# Opioid_-_Power_-_rev_A0.net
KiCad netlist of a schematic drawn in Altium Designer
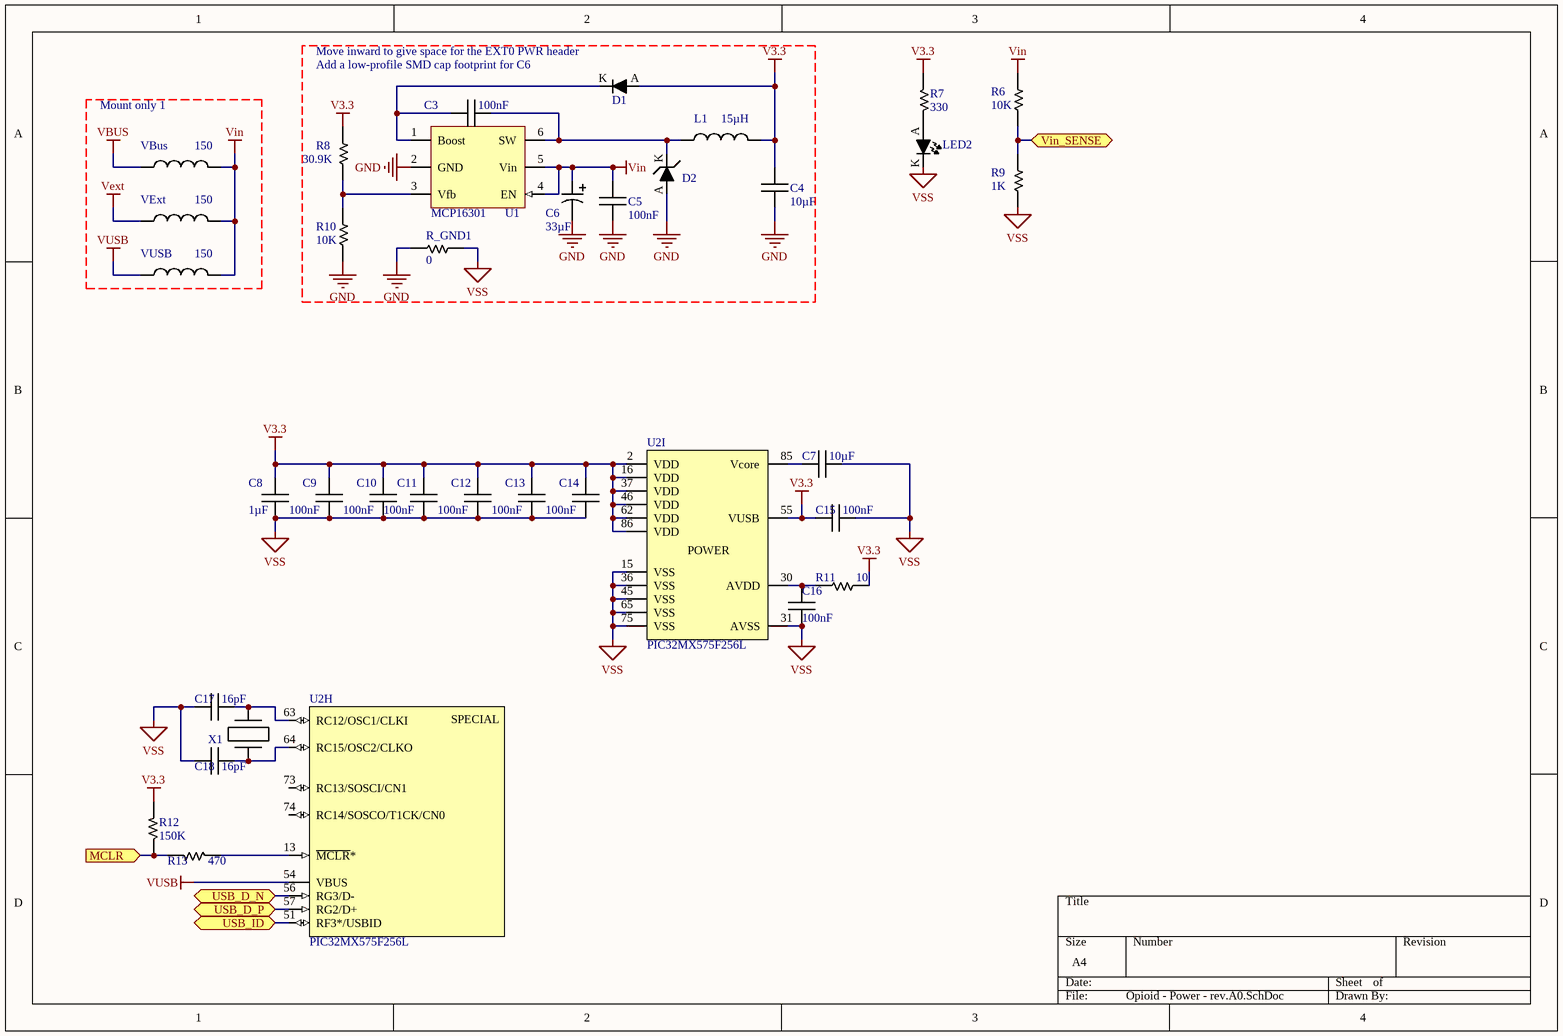
[diagram p0: Opioid - Power - rev.A0.SchDoc]

(export (version "E")
  (design (tool "Eeschema 10.0.6"))
  (components
    (comp (ref "C3") (value "100nF") (footprint "CAPC1608N") (libsource (lib "Megaxone") (part "Capacitor")))
    (comp (ref "C4") (value "10µF") (footprint "CAPC2012N") (libsource (lib "Megaxone") (part "Capacitor")))
    (comp (ref "C5") (value "100nF") (footprint "CAPC1608N") (libsource (lib "Megaxone") (part "Capacitor")))
    (comp (ref "C6")
      (value "33µF")
      (footprint "CAPPR2-5x11")
      (libsource (lib "Megaxone") (part "Capacitor Polarised"))
    )
    (comp (ref "C7") (value "10µF") (footprint "CAPC2012N") (libsource (lib "Megaxone") (part "Capacitor")))
    (comp (ref "C8") (value "1µF") (footprint "CAPC1608N") (libsource (lib "Megaxone") (part "Capacitor")))
    (comp (ref "C9") (value "100nF") (footprint "CAPC1608N") (libsource (lib "Megaxone") (part "Capacitor")))
    (comp (ref "C10") (value "100nF") (footprint "CAPC1608N") (libsource (lib "Megaxone") (part "Capacitor")))
    (comp (ref "C11") (value "100nF") (footprint "CAPC1608N") (libsource (lib "Megaxone") (part "Capacitor")))
    (comp (ref "C12") (value "100nF") (footprint "CAPC1608N") (libsource (lib "Megaxone") (part "Capacitor")))
    (comp (ref "C13") (value "100nF") (footprint "CAPC1608N") (libsource (lib "Megaxone") (part "Capacitor")))
    (comp (ref "C14") (value "100nF") (footprint "CAPC1608N") (libsource (lib "Megaxone") (part "Capacitor")))
    (comp (ref "C15") (value "100nF") (footprint "CAPC1608N") (libsource (lib "Megaxone") (part "Capacitor")))
    (comp (ref "C16") (value "100nF") (footprint "CAPC1608N") (libsource (lib "Megaxone") (part "Capacitor")))
    (comp (ref "C17") (value "16pF") (footprint "CAPC2012N") (libsource (lib "Megaxone") (part "Capacitor")))
    (comp (ref "C18") (value "16pF") (footprint "CAPC2012N") (libsource (lib "Megaxone") (part "Capacitor")))
    (comp (ref "D1") (value "Diode") (footprint "SOT323") (libsource (lib "Megaxone") (part "Diode")))
    (comp (ref "D2")
      (value "Schottky Diode")
      (footprint "DO-214AC")
      (libsource (lib "Megaxone") (part "Schottky Diode"))
    )
    (comp (ref "L1")
      (value "15µH")
      (footprint "INDUCTOR 6×6mm Taiyo Yuden")
      (libsource (lib "Megaxone") (part "Inductor"))
    )
    (comp (ref "LED2") (value "~") (footprint "LED 1608m") (libsource (lib "Megaxone") (part "LED")))
    (comp (ref "R6") (value "10K") (footprint "RESC1608N") (libsource (lib "") (part "Resistor_1")))
    (comp (ref "R7") (value "330") (footprint "RESC1608N") (libsource (lib "") (part "Resistor_2")))
    (comp (ref "R8") (value "30.9K") (footprint "RESC1608N") (libsource (lib "") (part "Resistor_1")))
    (comp (ref "R9") (value "1K") (footprint "RESC1608N") (libsource (lib "") (part "Resistor_1")))
    (comp (ref "R10") (value "10K") (footprint "RESC1608N") (libsource (lib "") (part "Resistor_1")))
    (comp (ref "R11") (value "10") (footprint "RESC1608N") (libsource (lib "Megaxone") (part "Resistor")))
    (comp (ref "R12") (value "150K") (footprint "RESC1608N") (libsource (lib "Megaxone") (part "Resistor")))
    (comp (ref "R13") (value "470") (footprint "RESC1608N") (libsource (lib "") (part "Resistor_3")))
    (comp (ref "R_GND1") (value "0") (footprint "RESC1608N") (libsource (lib "Megaxone") (part "Resistor")))
    (comp (ref "U1")
      (value "MCP16301")
      (footprint "SOT23-6_N")
      (libsource (lib "Megaxone") (part "MCP16301"))
    )
    (comp (ref "U2")
      (value "PIC32MX575F256L")
      (footprint "TQFP-PT100_N")
      (libsource (lib "Megaxone") (part "PIC32MX575F256L"))
    )
    (comp (ref "VBus") (value "150") (footprint "INDC1608N") (libsource (lib "Megaxone") (part "Inductor")))
    (comp (ref "VExt") (value "150") (footprint "INDC1608N") (libsource (lib "Megaxone") (part "Inductor")))
    (comp (ref "VUSB") (value "150") (footprint "INDC1608N") (libsource (lib "Megaxone") (part "Inductor")))
    (comp (ref "X1")
      (value "Crystal")
      (footprint "BCY-W2/D3.1")
      (libsource (lib "Megaxone") (part "Crystal"))
    )
  )
  (nets
    (net (code "1") (name "/MCLR") (class "Default")
      (node (ref "R12") (pin "1") (pinfunction "1_1") (pintype "passive"))
      (node (ref "R13") (pin "2") (pinfunction "2_2") (pintype "passive"))
    )
    (net (code "2") (name "/USB_D_N") (class "Default")
      (node (ref "U2") (pin "56") (pinfunction "RG3/D-_56") (pintype "input"))
    )
    (net (code "3") (name "/USB_D_P") (class "Default")
      (node (ref "U2") (pin "57") (pinfunction "RG2/D+_57") (pintype "input"))
    )
    (net (code "4") (name "/USB_ID") (class "Default")
      (node (ref "U2") (pin "51") (pinfunction "RF3*/USBID_51") (pintype "bidirectional"))
    )
    (net (code "5") (name "/Vin_SENSE") (class "Default")
      (node (ref "R6") (pin "1") (pinfunction "1_1") (pintype "passive"))
      (node (ref "R9") (pin "2") (pinfunction "2_2") (pintype "passive"))
    )
    (net (code "6") (name "GND") (class "Default")
      (node (ref "C4") (pin "1") (pinfunction "1_1") (pintype "passive"))
      (node (ref "C5") (pin "2") (pinfunction "2_2") (pintype "passive"))
      (node (ref "C6") (pin "2") (pinfunction "2_2") (pintype "passive"))
      (node (ref "D2") (pin "A") (pinfunction "Anode_A") (pintype "power_in"))
      (node (ref "R10") (pin "1") (pinfunction "1_1") (pintype "passive"))
      (node (ref "R_GND1") (pin "1") (pinfunction "1_1") (pintype "passive"))
      (node (ref "U1") (pin "2") (pinfunction "GND_2") (pintype "power_in"))
    )
    (net (code "7") (name "Net-(D2-Kathode)") (class "Default")
      (node (ref "C3") (pin "1") (pinfunction "1_1") (pintype "passive"))
      (node (ref "D2") (pin "K") (pinfunction "Kathode_K") (pintype "power_in"))
      (node (ref "L1") (pin "1") (pinfunction "1_1") (pintype "passive"))
      (node (ref "U1") (pin "6") (pinfunction "SW_6") (pintype "power_in"))
    )
    (net (code "8") (name "Net-(LED2-PadA)") (class "Default")
      (node (ref "LED2") (pin "A") (pinfunction "A_A") (pintype "passive"))
      (node (ref "R7") (pin "2") (pinfunction "2_2") (pintype "passive"))
    )
    (net (code "9") (name "Net-(U1-Boost)") (class "Default")
      (node (ref "C3") (pin "2") (pinfunction "2_2") (pintype "passive"))
      (node (ref "D1") (pin "K") (pinfunction "K_K") (pintype "power_in"))
      (node (ref "U1") (pin "1") (pinfunction "Boost_1") (pintype "passive"))
    )
    (net (code "10") (name "Net-(U1-Vfb)") (class "Default")
      (node (ref "R10") (pin "2") (pinfunction "2_2") (pintype "passive"))
      (node (ref "R8") (pin "1") (pinfunction "1_1") (pintype "passive"))
      (node (ref "U1") (pin "3") (pinfunction "Vfb_3") (pintype "passive"))
    )
    (net (code "11") (name "Net-(U2H-RC12{slash}OSC1{slash}CLKI)") (class "Default")
      (node (ref "C17") (pin "1") (pinfunction "1_1") (pintype "passive"))
      (node (ref "U2") (pin "63") (pinfunction "RC12/OSC1/CLKI_63") (pintype "bidirectional"))
      (node (ref "X1") (pin "2") (pinfunction "2_2") (pintype "passive"))
    )
    (net (code "12") (name "Net-(U2H-RC15{slash}OSC2{slash}CLKO)") (class "Default")
      (node (ref "C18") (pin "1") (pinfunction "1_1") (pintype "passive"))
      (node (ref "U2") (pin "64") (pinfunction "RC15/OSC2/CLKO_64") (pintype "bidirectional"))
      (node (ref "X1") (pin "1") (pinfunction "1_1") (pintype "passive"))
    )
    (net (code "13") (name "Net-(U2H-~{MCLR}*)") (class "Default")
      (node (ref "R13") (pin "1") (pinfunction "1_1") (pintype "passive"))
      (node (ref "U2") (pin "13") (pinfunction "~{MCLR}*_13") (pintype "input"))
    )
    (net (code "14") (name "Net-(U2I-AVDD)") (class "Default")
      (node (ref "C16") (pin "2") (pinfunction "2_2") (pintype "passive"))
      (node (ref "R11") (pin "1") (pinfunction "1_1") (pintype "passive"))
      (node (ref "U2") (pin "30") (pinfunction "AVDD_30") (pintype "power_in"))
    )
    (net (code "15") (name "Net-(U2I-Vcore)") (class "Default")
      (node (ref "C7") (pin "2") (pinfunction "2_2") (pintype "passive"))
      (node (ref "U2") (pin "85") (pinfunction "Vcore_85") (pintype "power_in"))
    )
    (net (code "16") (name "V3.3") (class "Default")
      (node (ref "C10") (pin "2") (pinfunction "2_2") (pintype "passive"))
      (node (ref "C11") (pin "2") (pinfunction "2_2") (pintype "passive"))
      (node (ref "C12") (pin "2") (pinfunction "2_2") (pintype "passive"))
      (node (ref "C13") (pin "2") (pinfunction "2_2") (pintype "passive"))
      (node (ref "C14") (pin "2") (pinfunction "2_2") (pintype "passive"))
      (node (ref "C15") (pin "2") (pinfunction "2_2") (pintype "passive"))
      (node (ref "C4") (pin "2") (pinfunction "2_2") (pintype "passive"))
      (node (ref "C8") (pin "2") (pinfunction "2_2") (pintype "passive"))
      (node (ref "C9") (pin "2") (pinfunction "2_2") (pintype "passive"))
      (node (ref "D1") (pin "A") (pinfunction "A_A") (pintype "power_in"))
      (node (ref "L1") (pin "2") (pinfunction "2_2") (pintype "passive"))
      (node (ref "R11") (pin "2") (pinfunction "2_2") (pintype "passive"))
      (node (ref "R12") (pin "2") (pinfunction "2_2") (pintype "passive"))
      (node (ref "R7") (pin "1") (pinfunction "1_1") (pintype "passive"))
      (node (ref "R8") (pin "2") (pinfunction "2_2") (pintype "passive"))
      (node (ref "U2") (pin "16") (pinfunction "VDD_16") (pintype "power_in"))
      (node (ref "U2") (pin "2") (pinfunction "VDD_2") (pintype "power_in"))
      (node (ref "U2") (pin "37") (pinfunction "VDD_37") (pintype "power_in"))
      (node (ref "U2") (pin "46") (pinfunction "VDD_46") (pintype "power_in"))
      (node (ref "U2") (pin "55") (pinfunction "VUSB_55") (pintype "power_in"))
      (node (ref "U2") (pin "62") (pinfunction "VDD_62") (pintype "power_in"))
      (node (ref "U2") (pin "86") (pinfunction "VDD_86") (pintype "power_in"))
    )
    (net (code "17") (name "VBUS") (class "Default")
      (node (ref "VBus") (pin "1") (pinfunction "1_1") (pintype "passive"))
    )
    (net (code "18") (name "VSS") (class "Default")
      (node (ref "C10") (pin "1") (pinfunction "1_1") (pintype "passive"))
      (node (ref "C11") (pin "1") (pinfunction "1_1") (pintype "passive"))
      (node (ref "C12") (pin "1") (pinfunction "1_1") (pintype "passive"))
      (node (ref "C13") (pin "1") (pinfunction "1_1") (pintype "passive"))
      (node (ref "C14") (pin "1") (pinfunction "1_1") (pintype "passive"))
      (node (ref "C15") (pin "1") (pinfunction "1_1") (pintype "passive"))
      (node (ref "C16") (pin "1") (pinfunction "1_1") (pintype "passive"))
      (node (ref "C17") (pin "2") (pinfunction "2_2") (pintype "passive"))
      (node (ref "C18") (pin "2") (pinfunction "2_2") (pintype "passive"))
      (node (ref "C7") (pin "1") (pinfunction "1_1") (pintype "passive"))
      (node (ref "C8") (pin "1") (pinfunction "1_1") (pintype "passive"))
      (node (ref "C9") (pin "1") (pinfunction "1_1") (pintype "passive"))
      (node (ref "LED2") (pin "K") (pinfunction "K_K") (pintype "passive"))
      (node (ref "R9") (pin "1") (pinfunction "1_1") (pintype "passive"))
      (node (ref "R_GND1") (pin "2") (pinfunction "2_2") (pintype "passive"))
      (node (ref "U2") (pin "15") (pinfunction "VSS_15") (pintype "power_in"))
      (node (ref "U2") (pin "31") (pinfunction "AVSS_31") (pintype "power_in"))
      (node (ref "U2") (pin "36") (pinfunction "VSS_36") (pintype "power_in"))
      (node (ref "U2") (pin "45") (pinfunction "VSS_45") (pintype "power_in"))
      (node (ref "U2") (pin "65") (pinfunction "VSS_65") (pintype "power_in"))
      (node (ref "U2") (pin "75") (pinfunction "VSS_75") (pintype "power_in"))
    )
    (net (code "19") (name "VUSB") (class "Default")
      (node (ref "U2") (pin "54") (pinfunction "VBUS_54") (pintype "passive"))
      (node (ref "VUSB") (pin "1") (pinfunction "1_1") (pintype "passive"))
    )
    (net (code "20") (name "Vext") (class "Default")
      (node (ref "VExt") (pin "1") (pinfunction "1_1") (pintype "passive"))
    )
    (net (code "21") (name "Vin") (class "Default")
      (node (ref "C5") (pin "1") (pinfunction "1_1") (pintype "passive"))
      (node (ref "C6") (pin "1") (pinfunction "1_1") (pintype "passive"))
      (node (ref "R6") (pin "2") (pinfunction "2_2") (pintype "passive"))
      (node (ref "U1") (pin "4") (pinfunction "EN_4") (pintype "input"))
      (node (ref "U1") (pin "5") (pinfunction "Vin_5") (pintype "power_in"))
      (node (ref "VBus") (pin "2") (pinfunction "2_2") (pintype "passive"))
      (node (ref "VExt") (pin "2") (pinfunction "2_2") (pintype "passive"))
      (node (ref "VUSB") (pin "2") (pinfunction "2_2") (pintype "passive"))
    )
    (net (code "22") (name "unconnected-(U2H-RC13{slash}SOSCI{slash}CN1-Pad73)") (class "Default")
      (node (ref "U2") (pin "73") (pinfunction "RC13/SOSCI/CN1_73") (pintype "bidirectional"))
    )
    (net (code "23") (name "unconnected-(U2H-RC14{slash}SOSCO{slash}T1CK{slash}CN0-Pad74)") (class "Default")
      (node (ref "U2") (pin "74") (pinfunction "RC14/SOSCO/T1CK/CN0_74") (pintype "bidirectional"))
    )
  )
)
